# PIC12F675_ADC_PWM.net
KiCad netlist of a schematic drawn in Altium Designer
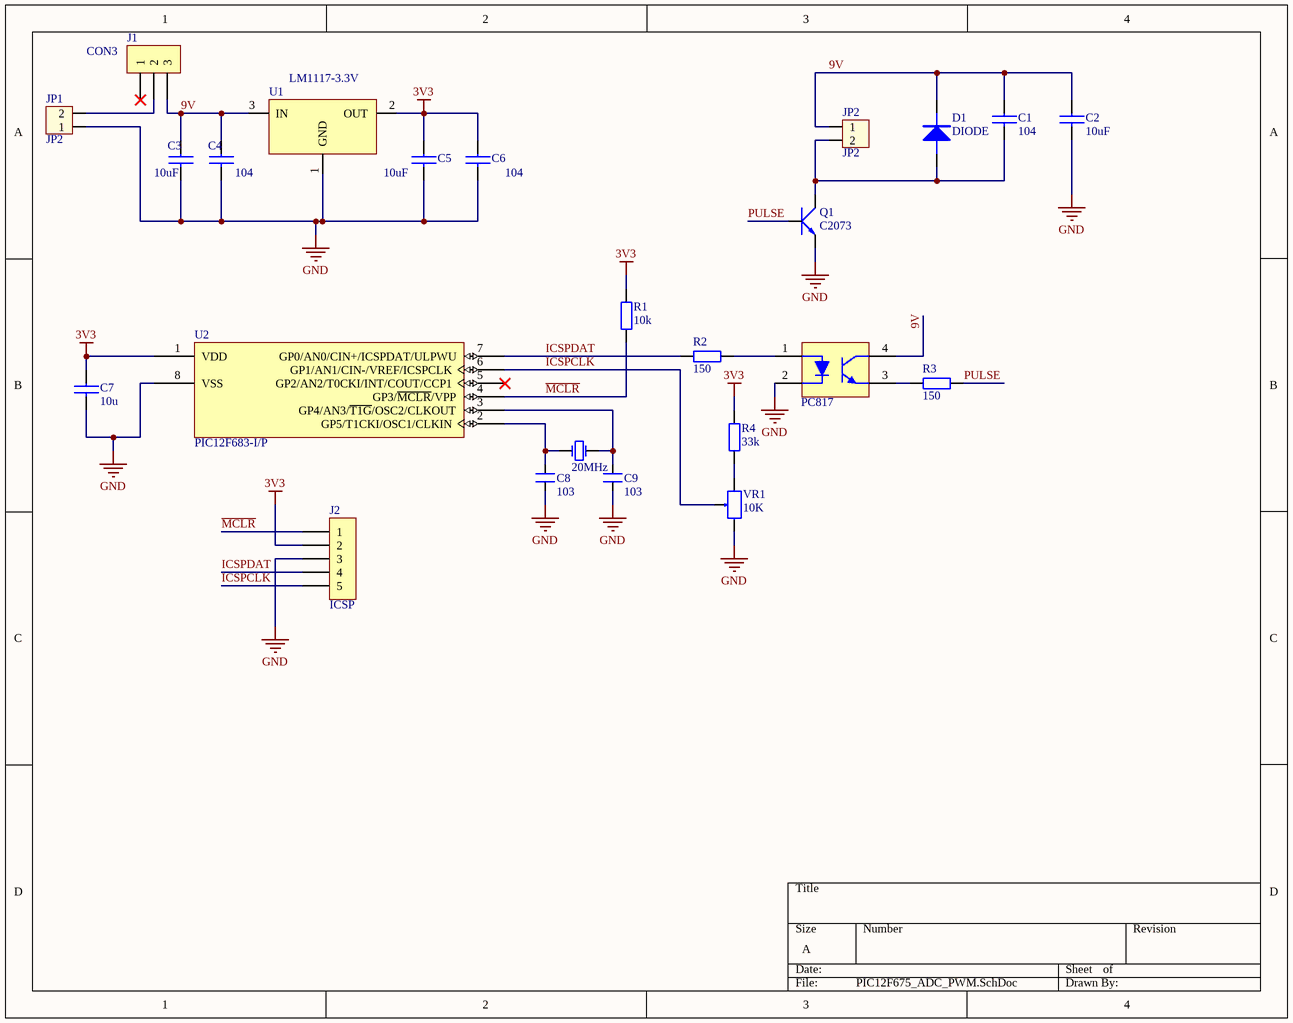
[diagram p0: PIC12F675_ADC_PWM.SchDoc]

(export (version "E")
  (design (tool "Eeschema 10.0.6"))
  (components
    (comp (ref "C1") (value "104") (footprint "0805") (libsource (lib "PML") (part "CAP 0805")))
    (comp (ref "C2") (value "10uF") (footprint "0805") (libsource (lib "PML") (part "CAP 0805")))
    (comp (ref "C3") (value "10uF") (footprint "0805") (libsource (lib "PML") (part "CAP 0805")))
    (comp (ref "C4") (value "104") (footprint "0805") (libsource (lib "PML") (part "CAP 0805")))
    (comp (ref "C5") (value "10uF") (footprint "0805") (libsource (lib "PML") (part "CAP 0805")))
    (comp (ref "C6") (value "104") (footprint "0805") (libsource (lib "PML") (part "CAP 0805")))
    (comp (ref "C7") (value "10u") (footprint "0805") (libsource (lib "PML") (part "CAP 0805")))
    (comp (ref "C8")
      (value "103")
      (footprint "CN1.5")
      (description "Cap np 682pF => 104pF")
      (libsource (lib "PML") (part "CN1.5"))
    )
    (comp (ref "C9")
      (value "103")
      (footprint "CN1.5")
      (description "Cap np 682pF => 104pF")
      (libsource (lib "PML") (part "CN1.5"))
    )
    (comp (ref "D1")
      (value "DIODE")
      (footprint "DIODE/NOM/0.5A")
      (description "Diode")
      (libsource (lib "PML") (part "DIODE"))
    )
    (comp (ref "J1")
      (value "CON3")
      (footprint "CON3")
      (description "Connector")
      (libsource (lib "PML") (part "CON3"))
    )
    (comp (ref "J2")
      (value "ICSP")
      (footprint "con5")
      (description "Connector")
      (libsource (lib "PML") (part "CON5"))
    )
    (comp (ref "JP1")
      (value "JP2")
      (footprint "CON2")
      (description "Connector 2")
      (libsource (lib "") (part "CON2_1"))
    )
    (comp (ref "JP2")
      (value "JP2")
      (footprint "CON2")
      (description "Connector 2")
      (libsource (lib "PML") (part "CON2"))
    )
    (comp (ref "P1")
      (value "PC817")
      (footprint "DIP-4")
      (description "NPN PHOTO General Purpose Amplifier")
      (fields (field (name "PUBLISHER") "Altium Limited"))
      (libsource (lib "PML") (part "PC817"))
    )
    (comp (ref "Q1")
      (value "C2073")
      (footprint "QTO-92")
      (description "NPN 600mW, ECB")
      (libsource (lib "Cty1") (part "C1815"))
    )
    (comp (ref "R1")
      (value "10k")
      (footprint "0805")
      (description "Resistor 1/4W")
      (libsource (lib "PML") (part "R1/4W"))
    )
    (comp (ref "R2")
      (value "150")
      (footprint "0805")
      (description "Resistor 1/4W")
      (libsource (lib "PML") (part "R1/4W"))
    )
    (comp (ref "R3")
      (value "150")
      (footprint "0805")
      (description "Resistor 1/4W")
      (libsource (lib "PML") (part "R1/4W"))
    )
    (comp (ref "R4")
      (value "33k")
      (footprint "0805")
      (description "Resistor 1/4W")
      (libsource (lib "PML") (part "R1/4W"))
    )
    (comp (ref "U1")
      (value "LM1117-3.3V")
      (footprint "SOT223-4N")
      (description "800mA Low-Dropout Linear Regulator")
      (fields (field (name "CREATOR") "Nguyen Ba Bien"))
      (libsource (lib "PML") (part "LM1117_1"))
    )
    (comp (ref "U2")
      (value "PIC12F683-I/P")
      (footprint "PDIP300-P8")
      (fields (field (name "MANUFACTURER") "Microchip"))
      (libsource (lib "Microchip PIC12") (part "PIC12F683-I/P"))
    )
    (comp (ref "VR1")
      (value "10K")
      (footprint "VR")
      (description "Var Resistor")
      (libsource (lib "PML") (part "Var Resitor"))
    )
    (comp (ref "Y1")
      (value "20MHz")
      (footprint "XT2")
      (description "Crystal Oscillator")
      (fields (field (name "PUBLISHER") "Altium Limited"))
      (libsource (lib "PML") (part "Crystal"))
    )
  )
  (nets
    (net (code "1") (name "/9V") (class "Default")
      (node (ref "C1") (pin "1") (pinfunction "1_1") (pintype "passive"))
      (node (ref "C2") (pin "1") (pinfunction "1_1") (pintype "passive"))
      (node (ref "C3") (pin "1") (pinfunction "1_1") (pintype "passive"))
      (node (ref "C4") (pin "1") (pinfunction "1_1") (pintype "passive"))
      (node (ref "D1") (pin "2") (pinfunction "2_2") (pintype "passive"))
      (node (ref "J1") (pin "3") (pinfunction "3_3") (pintype "passive"))
      (node (ref "JP2") (pin "1") (pinfunction "1_1") (pintype "passive"))
      (node (ref "P1") (pin "4") (pinfunction "4_4") (pintype "passive"))
      (node (ref "U1") (pin "3") (pinfunction "IN_3") (pintype "passive"))
    )
    (net (code "2") (name "/ICSPCLK") (class "Default")
      (node (ref "J2") (pin "5") (pinfunction "5_5") (pintype "passive"))
      (node (ref "U2") (pin "6") (pinfunction "GP1/AN1/CIN-/VREF/ICSPCLK_6") (pintype "bidirectional"))
      (node (ref "VR1") (pin "2") (pinfunction "2_2") (pintype "passive"))
    )
    (net (code "3") (name "/ICSPDAT") (class "Default")
      (node (ref "J2") (pin "4") (pinfunction "4_4") (pintype "passive"))
      (node (ref "R2") (pin "1") (pinfunction "1_1") (pintype "passive"))
      (node (ref "U2") (pin "7") (pinfunction "GP0/AN0/CIN+/ICSPDAT/ULPWU_7") (pintype "bidirectional"))
    )
    (net (code "4") (name "/PULSE") (class "Default")
      (node (ref "Q1") (pin "3") (pinfunction "B_3") (pintype "passive"))
      (node (ref "R3") (pin "2") (pinfunction "2_2") (pintype "passive"))
    )
    (net (code "5") (name "/~{MCLR}") (class "Default")
      (node (ref "J2") (pin "1") (pinfunction "1_1") (pintype "passive"))
      (node (ref "R1") (pin "1") (pinfunction "1_1") (pintype "passive"))
      (node (ref "U2") (pin "4") (pinfunction "GP3/~{MCLR}/VPP_4") (pintype "bidirectional"))
    )
    (net (code "6") (name "3V3") (class "Default")
      (node (ref "C5") (pin "1") (pinfunction "1_1") (pintype "passive"))
      (node (ref "C6") (pin "1") (pinfunction "1_1") (pintype "passive"))
      (node (ref "C7") (pin "1") (pinfunction "1_1") (pintype "passive"))
      (node (ref "J2") (pin "2") (pinfunction "2_2") (pintype "passive"))
      (node (ref "R1") (pin "2") (pinfunction "2_2") (pintype "passive"))
      (node (ref "R4") (pin "2") (pinfunction "2_2") (pintype "passive"))
      (node (ref "U1") (pin "2") (pinfunction "OUT_2") (pintype "passive"))
      (node (ref "U2") (pin "1") (pinfunction "VDD_1") (pintype "power_in"))
    )
    (net (code "7") (name "GND") (class "Default")
      (node (ref "C2") (pin "2") (pinfunction "2_2") (pintype "passive"))
      (node (ref "C3") (pin "2") (pinfunction "2_2") (pintype "passive"))
      (node (ref "C4") (pin "2") (pinfunction "2_2") (pintype "passive"))
      (node (ref "C5") (pin "2") (pinfunction "2_2") (pintype "passive"))
      (node (ref "C6") (pin "2") (pinfunction "2_2") (pintype "passive"))
      (node (ref "C7") (pin "2") (pinfunction "2_2") (pintype "passive"))
      (node (ref "C8") (pin "1") (pinfunction "1_1") (pintype "passive"))
      (node (ref "C9") (pin "1") (pinfunction "1_1") (pintype "passive"))
      (node (ref "J2") (pin "3") (pinfunction "3_3") (pintype "passive"))
      (node (ref "JP1") (pin "1") (pinfunction "1_1") (pintype "passive"))
      (node (ref "P1") (pin "2") (pinfunction "2_2") (pintype "passive"))
      (node (ref "Q1") (pin "1") (pinfunction "E_1") (pintype "passive"))
      (node (ref "U1") (pin "1") (pinfunction "GND_1") (pintype "passive"))
      (node (ref "U2") (pin "8") (pinfunction "VSS_8") (pintype "power_in"))
      (node (ref "VR1") (pin "1") (pinfunction "1_1") (pintype "passive"))
    )
    (net (code "8") (name "Net-(J1-Pad2)") (class "Default")
      (node (ref "J1") (pin "2") (pinfunction "2_2") (pintype "passive"))
      (node (ref "JP1") (pin "2") (pinfunction "2_2") (pintype "passive"))
    )
    (net (code "9") (name "Net-(P1-Pad1)") (class "Default")
      (node (ref "P1") (pin "1") (pinfunction "1_1") (pintype "passive"))
      (node (ref "R2") (pin "2") (pinfunction "2_2") (pintype "passive"))
    )
    (net (code "10") (name "Net-(P1-Pad3)") (class "Default")
      (node (ref "P1") (pin "3") (pinfunction "3_3") (pintype "passive"))
      (node (ref "R3") (pin "1") (pinfunction "1_1") (pintype "passive"))
    )
    (net (code "11") (name "Net-(Q1-C)") (class "Default")
      (node (ref "C1") (pin "2") (pinfunction "2_2") (pintype "passive"))
      (node (ref "D1") (pin "1") (pinfunction "1_1") (pintype "passive"))
      (node (ref "JP2") (pin "2") (pinfunction "2_2") (pintype "passive"))
      (node (ref "Q1") (pin "2") (pinfunction "C_2") (pintype "passive"))
    )
    (net (code "12") (name "Net-(R4-Pad1)") (class "Default")
      (node (ref "R4") (pin "1") (pinfunction "1_1") (pintype "passive"))
      (node (ref "VR1") (pin "3") (pinfunction "3_3") (pintype "passive"))
    )
    (net (code "13") (name "Net-(U2-GP4{slash}AN3{slash}~{T1G}{slash}OSC2{slash}CLKOUT)") (class "Default")
      (node (ref "C9") (pin "2") (pinfunction "2_2") (pintype "passive"))
      (node (ref "U2") (pin "3") (pinfunction "GP4/AN3/~{T1G}/OSC2/CLKOUT_3") (pintype "bidirectional"))
      (node (ref "Y1") (pin "2") (pinfunction "OSC2_2") (pintype "passive"))
    )
    (net (code "14") (name "Net-(U2-GP5{slash}T1CKI{slash}OSC1{slash}CLKIN)") (class "Default")
      (node (ref "C8") (pin "2") (pinfunction "2_2") (pintype "passive"))
      (node (ref "U2") (pin "2") (pinfunction "GP5/T1CKI/OSC1/CLKIN_2") (pintype "bidirectional"))
      (node (ref "Y1") (pin "1") (pinfunction "OSC1_1") (pintype "passive"))
    )
    (net (code "15") (name "unconnected-(J1-Pad1)") (class "Default")
      (node (ref "J1") (pin "1") (pinfunction "1_1") (pintype "passive+no_connect"))
    )
    (net (code "16") (name "unconnected-(U2-GP2{slash}AN2{slash}T0CKI{slash}INT{slash}COUT{slash}CCP1-Pad5)") (class "Default")
      (node (ref "U2") (pin "5") (pinfunction "GP2/AN2/T0CKI/INT/COUT/CCP1_5") (pintype "bidirectional+no_connect"))
    )
  )
)
